# main.net
KiCad netlist of a schematic drawn in EAGLE
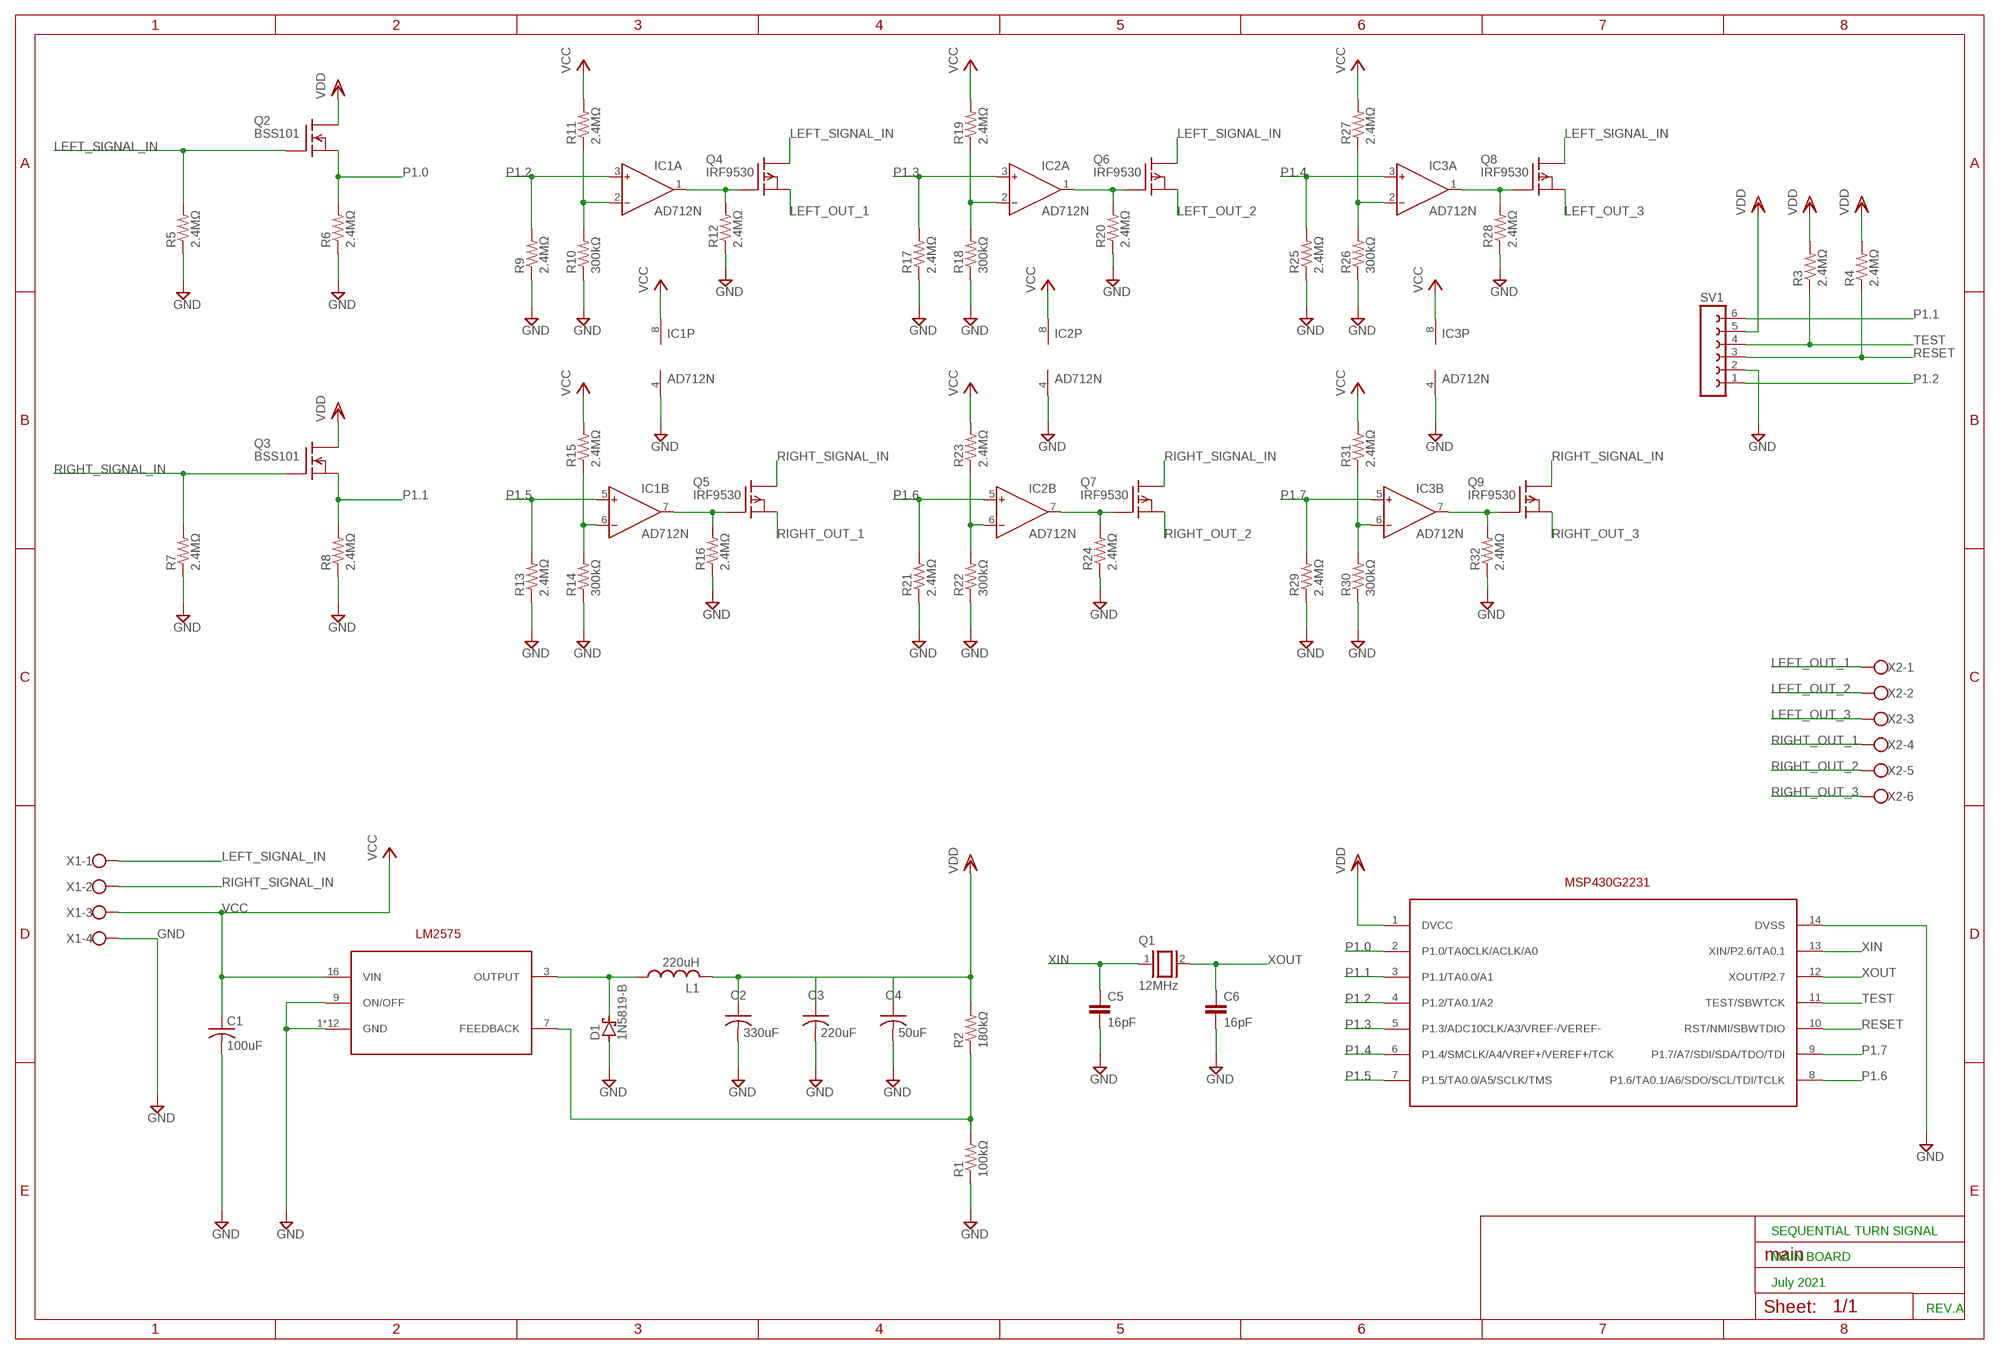
[diagram p0: schematic, sheet 1]

(export (version "E")
  (design (tool "Eeschema 10.0.6"))
  (components
    (comp (ref "C1")
      (value "100uF")
      (footprint "eagle-import:C025-050X050")
      (libsource (lib "eagle-import") (part "C-US025-050X050"))
    )
    (comp (ref "C2")
      (value "330uF")
      (footprint "eagle-import:C025-050X050")
      (libsource (lib "eagle-import") (part "C-US025-050X050"))
    )
    (comp (ref "C3")
      (value "220uF")
      (footprint "eagle-import:C025-050X050")
      (libsource (lib "eagle-import") (part "C-US025-050X050"))
    )
    (comp (ref "C4")
      (value "50uF")
      (footprint "eagle-import:C025-050X050")
      (libsource (lib "eagle-import") (part "C-US025-050X050"))
    )
    (comp (ref "C5")
      (value "16pF")
      (footprint "eagle-import:C025-024X044")
      (libsource (lib "eagle-import") (part "C-EU025-024X044"))
    )
    (comp (ref "C6")
      (value "16pF")
      (footprint "eagle-import:C025-024X044")
      (libsource (lib "eagle-import") (part "C-EU025-024X044"))
    )
    (comp (ref "D1")
      (value "1N5819-B")
      (footprint "eagle-import:DO41-7.6")
      (libsource (lib "eagle-import") (part "1N5819-B"))
    )
    (comp (ref "IC1")
      (value "AD712N")
      (footprint "eagle-import:DIL08")
      (fields (field (name "MF") "ALTERA CORPORATION") (field (name "MPN") "AD712JNZ"))
      (libsource (lib "eagle-import") (part "AD712N"))
    )
    (comp (ref "IC2")
      (value "AD712N")
      (footprint "eagle-import:DIL08")
      (fields (field (name "MF") "ALTERA CORPORATION") (field (name "MPN") "AD712JNZ"))
      (libsource (lib "eagle-import") (part "AD712N"))
    )
    (comp (ref "IC3")
      (value "AD712N")
      (footprint "eagle-import:DIL08")
      (fields (field (name "MF") "ALTERA CORPORATION") (field (name "MPN") "AD712JNZ"))
      (libsource (lib "eagle-import") (part "AD712N"))
    )
    (comp (ref "L1")
      (value "220uH")
      (footprint "eagle-import:6000-XXXX-RC")
      (libsource (lib "eagle-import") (part "L-US6000-XXX-RC"))
    )
    (comp (ref "Q1")
      (value "12MHz")
      (footprint "eagle-import:Q")
      (libsource (lib "eagle-import") (part "XTAL"))
    )
    (comp (ref "Q2")
      (value "BSS101")
      (footprint "eagle-import:TO92")
      (libsource (lib "eagle-import") (part "BSS101"))
    )
    (comp (ref "Q3")
      (value "BSS101")
      (footprint "eagle-import:TO92")
      (libsource (lib "eagle-import") (part "BSS101"))
    )
    (comp (ref "Q4")
      (value "IRF9530")
      (footprint "eagle-import:TO220")
      (libsource (lib "eagle-import") (part "IRF9530"))
    )
    (comp (ref "Q5")
      (value "IRF9530")
      (footprint "eagle-import:TO220")
      (libsource (lib "eagle-import") (part "IRF9530"))
    )
    (comp (ref "Q6")
      (value "IRF9530")
      (footprint "eagle-import:TO220")
      (libsource (lib "eagle-import") (part "IRF9530"))
    )
    (comp (ref "Q7")
      (value "IRF9530")
      (footprint "eagle-import:TO220")
      (libsource (lib "eagle-import") (part "IRF9530"))
    )
    (comp (ref "Q8")
      (value "IRF9530")
      (footprint "eagle-import:TO220")
      (libsource (lib "eagle-import") (part "IRF9530"))
    )
    (comp (ref "Q9")
      (value "IRF9530")
      (footprint "eagle-import:TO220")
      (libsource (lib "eagle-import") (part "IRF9530"))
    )
    (comp (ref "R1")
      (value "100kΩ")
      (footprint "eagle-import:0207_12")
      (libsource (lib "eagle-import") (part "R-US_0207/12"))
    )
    (comp (ref "R2")
      (value "180kΩ")
      (footprint "eagle-import:0207_12")
      (libsource (lib "eagle-import") (part "R-US_0207/12"))
    )
    (comp (ref "R3")
      (value "2.4MΩ")
      (footprint "eagle-import:0207_12")
      (libsource (lib "eagle-import") (part "R-US_0207/12"))
    )
    (comp (ref "R4")
      (value "2.4MΩ")
      (footprint "eagle-import:0207_12")
      (libsource (lib "eagle-import") (part "R-US_0207/12"))
    )
    (comp (ref "R5")
      (value "2.4MΩ")
      (footprint "eagle-import:0207_12")
      (libsource (lib "eagle-import") (part "R-US_0207/12"))
    )
    (comp (ref "R6")
      (value "2.4MΩ")
      (footprint "eagle-import:0207_12")
      (libsource (lib "eagle-import") (part "R-US_0207/12"))
    )
    (comp (ref "R7")
      (value "2.4MΩ")
      (footprint "eagle-import:0207_12")
      (libsource (lib "eagle-import") (part "R-US_0207/12"))
    )
    (comp (ref "R8")
      (value "2.4MΩ")
      (footprint "eagle-import:0207_12")
      (libsource (lib "eagle-import") (part "R-US_0207/12"))
    )
    (comp (ref "R9")
      (value "2.4MΩ")
      (footprint "eagle-import:0207_12")
      (libsource (lib "eagle-import") (part "R-US_0207/12"))
    )
    (comp (ref "R10")
      (value "300kΩ")
      (footprint "eagle-import:0207_12")
      (libsource (lib "eagle-import") (part "R-US_0207/12"))
    )
    (comp (ref "R11")
      (value "2.4MΩ")
      (footprint "eagle-import:0207_12")
      (libsource (lib "eagle-import") (part "R-US_0207/12"))
    )
    (comp (ref "R12")
      (value "2.4MΩ")
      (footprint "eagle-import:0207_12")
      (libsource (lib "eagle-import") (part "R-US_0207/12"))
    )
    (comp (ref "R13")
      (value "2.4MΩ")
      (footprint "eagle-import:0207_12")
      (libsource (lib "eagle-import") (part "R-US_0207/12"))
    )
    (comp (ref "R14")
      (value "300kΩ")
      (footprint "eagle-import:0207_12")
      (libsource (lib "eagle-import") (part "R-US_0207/12"))
    )
    (comp (ref "R15")
      (value "2.4MΩ")
      (footprint "eagle-import:0207_12")
      (libsource (lib "eagle-import") (part "R-US_0207/12"))
    )
    (comp (ref "R16")
      (value "2.4MΩ")
      (footprint "eagle-import:0207_12")
      (libsource (lib "eagle-import") (part "R-US_0207/12"))
    )
    (comp (ref "R17")
      (value "2.4MΩ")
      (footprint "eagle-import:0207_12")
      (libsource (lib "eagle-import") (part "R-US_0207/12"))
    )
    (comp (ref "R18")
      (value "300kΩ")
      (footprint "eagle-import:0207_12")
      (libsource (lib "eagle-import") (part "R-US_0207/12"))
    )
    (comp (ref "R19")
      (value "2.4MΩ")
      (footprint "eagle-import:0207_12")
      (libsource (lib "eagle-import") (part "R-US_0207/12"))
    )
    (comp (ref "R20")
      (value "2.4MΩ")
      (footprint "eagle-import:0207_12")
      (libsource (lib "eagle-import") (part "R-US_0207/12"))
    )
    (comp (ref "R21")
      (value "2.4MΩ")
      (footprint "eagle-import:0207_12")
      (libsource (lib "eagle-import") (part "R-US_0207/12"))
    )
    (comp (ref "R22")
      (value "300kΩ")
      (footprint "eagle-import:0207_12")
      (libsource (lib "eagle-import") (part "R-US_0207/12"))
    )
    (comp (ref "R23")
      (value "2.4MΩ")
      (footprint "eagle-import:0207_12")
      (libsource (lib "eagle-import") (part "R-US_0207/12"))
    )
    (comp (ref "R24")
      (value "2.4MΩ")
      (footprint "eagle-import:0207_12")
      (libsource (lib "eagle-import") (part "R-US_0207/12"))
    )
    (comp (ref "R25")
      (value "2.4MΩ")
      (footprint "eagle-import:0207_12")
      (libsource (lib "eagle-import") (part "R-US_0207/12"))
    )
    (comp (ref "R26")
      (value "300kΩ")
      (footprint "eagle-import:0207_12")
      (libsource (lib "eagle-import") (part "R-US_0207/12"))
    )
    (comp (ref "R27")
      (value "2.4MΩ")
      (footprint "eagle-import:0207_12")
      (libsource (lib "eagle-import") (part "R-US_0207/12"))
    )
    (comp (ref "R28")
      (value "2.4MΩ")
      (footprint "eagle-import:0207_12")
      (libsource (lib "eagle-import") (part "R-US_0207/12"))
    )
    (comp (ref "R29")
      (value "2.4MΩ")
      (footprint "eagle-import:0207_12")
      (libsource (lib "eagle-import") (part "R-US_0207/12"))
    )
    (comp (ref "R30")
      (value "300kΩ")
      (footprint "eagle-import:0207_12")
      (libsource (lib "eagle-import") (part "R-US_0207/12"))
    )
    (comp (ref "R31")
      (value "2.4MΩ")
      (footprint "eagle-import:0207_12")
      (libsource (lib "eagle-import") (part "R-US_0207/12"))
    )
    (comp (ref "R32")
      (value "2.4MΩ")
      (footprint "eagle-import:0207_12")
      (libsource (lib "eagle-import") (part "R-US_0207/12"))
    )
    (comp (ref "SV1")
      (value "FE06-1")
      (footprint "eagle-import:FE06")
      (libsource (lib "eagle-import") (part "FE06-1"))
    )
    (comp (ref "U$1")
      (value "MSP430G2231PDIP14")
      (footprint "eagle-import:DIP762W53P254L1969H508Q14B")
      (libsource (lib "eagle-import") (part "MSP430G2231PDIP14"))
    )
    (comp (ref "U$2")
      (value "LM2575PDIP16")
      (footprint "eagle-import:DIP762W53P254L1969H508Q16B")
      (libsource (lib "eagle-import") (part "LM2575PDIP16"))
    )
    (comp (ref "X1")
      (value "W237-4")
      (footprint "eagle-import:W237-4")
      (libsource (lib "eagle-import") (part "W237-4"))
    )
    (comp (ref "X2")
      (value "W237-6")
      (footprint "eagle-import:W237-6")
      (libsource (lib "eagle-import") (part "W237-6"))
    )
  )
  (nets
    (net (code "1") (name "/LEFT_OUT_1") (class "Default")
      (node (ref "Q4") (pin "3") (pinfunction "S_3") (pintype "passive"))
      (node (ref "X2") (pin "1") (pinfunction "KL_1") (pintype "passive"))
    )
    (net (code "2") (name "/LEFT_OUT_2") (class "Default")
      (node (ref "Q6") (pin "3") (pinfunction "S_3") (pintype "passive"))
      (node (ref "X2") (pin "2") (pinfunction "KL_2") (pintype "passive"))
    )
    (net (code "3") (name "/LEFT_OUT_3") (class "Default")
      (node (ref "Q8") (pin "3") (pinfunction "S_3") (pintype "passive"))
      (node (ref "X2") (pin "3") (pinfunction "KL_3") (pintype "passive"))
    )
    (net (code "4") (name "/LEFT_SIGNAL_IN") (class "Default")
      (node (ref "Q2") (pin "2") (pinfunction "G_2") (pintype "passive"))
      (node (ref "Q4") (pin "2") (pinfunction "D_2") (pintype "passive"))
      (node (ref "Q6") (pin "2") (pinfunction "D_2") (pintype "passive"))
      (node (ref "Q8") (pin "2") (pinfunction "D_2") (pintype "passive"))
      (node (ref "R5") (pin "2") (pinfunction "2_2") (pintype "passive"))
      (node (ref "X1") (pin "1") (pinfunction "KL_1") (pintype "passive"))
    )
    (net (code "5") (name "/P1.0") (class "Default")
      (node (ref "Q2") (pin "1") (pinfunction "S_1") (pintype "passive"))
      (node (ref "R6") (pin "2") (pinfunction "2_2") (pintype "passive"))
      (node (ref "U$1") (pin "2") (pinfunction "P1.0/TA0CLK/ACLK/A0_2") (pintype "bidirectional"))
    )
    (net (code "6") (name "/P1.1") (class "Default")
      (node (ref "Q3") (pin "1") (pinfunction "S_1") (pintype "passive"))
      (node (ref "R8") (pin "2") (pinfunction "2_2") (pintype "passive"))
      (node (ref "SV1") (pin "6") (pinfunction "6_6") (pintype "passive"))
      (node (ref "U$1") (pin "3") (pinfunction "P1.1/TA0.0/A1_3") (pintype "bidirectional"))
    )
    (net (code "7") (name "/P1.2") (class "Default")
      (node (ref "IC1") (pin "3") (pinfunction "IN+_3") (pintype "input"))
      (node (ref "R9") (pin "2") (pinfunction "2_2") (pintype "passive"))
      (node (ref "SV1") (pin "1") (pinfunction "1_1") (pintype "passive"))
      (node (ref "U$1") (pin "4") (pinfunction "P1.2/TA0.1/A2_4") (pintype "bidirectional"))
    )
    (net (code "8") (name "/P1.3") (class "Default")
      (node (ref "IC2") (pin "3") (pinfunction "IN+_3") (pintype "input"))
      (node (ref "R17") (pin "2") (pinfunction "2_2") (pintype "passive"))
      (node (ref "U$1") (pin "5") (pinfunction "P1.3/ADC10CLK/A3/VREF-/VEREF-_5") (pintype "bidirectional"))
    )
    (net (code "9") (name "/P1.4") (class "Default")
      (node (ref "IC3") (pin "3") (pinfunction "IN+_3") (pintype "input"))
      (node (ref "R25") (pin "2") (pinfunction "2_2") (pintype "passive"))
      (node (ref "U$1") (pin "6") (pinfunction "P1.4/SMCLK/A4/VREF+/VEREF+/TCK_6") (pintype "bidirectional"))
    )
    (net (code "10") (name "/P1.5") (class "Default")
      (node (ref "IC1") (pin "5") (pinfunction "IN+_5") (pintype "input"))
      (node (ref "R13") (pin "2") (pinfunction "2_2") (pintype "passive"))
      (node (ref "U$1") (pin "7") (pinfunction "P1.5/TA0.0/A5/SCLK/TMS_7") (pintype "bidirectional"))
    )
    (net (code "11") (name "/P1.6") (class "Default")
      (node (ref "IC2") (pin "5") (pinfunction "IN+_5") (pintype "input"))
      (node (ref "R21") (pin "2") (pinfunction "2_2") (pintype "passive"))
      (node (ref "U$1") (pin "8") (pinfunction "P1.6/TA0.1/A6/SDO/SCL/TDI/TCLK_8") (pintype "bidirectional"))
    )
    (net (code "12") (name "/P1.7") (class "Default")
      (node (ref "IC3") (pin "5") (pinfunction "IN+_5") (pintype "input"))
      (node (ref "R29") (pin "2") (pinfunction "2_2") (pintype "passive"))
      (node (ref "U$1") (pin "9") (pinfunction "P1.7/A7/SDI/SDA/TDO/TDI_9") (pintype "bidirectional"))
    )
    (net (code "13") (name "/RESET") (class "Default")
      (node (ref "R4") (pin "1") (pinfunction "1_1") (pintype "passive"))
      (node (ref "SV1") (pin "3") (pinfunction "3_3") (pintype "passive"))
      (node (ref "U$1") (pin "10") (pinfunction "RST/NMI/SBWTDIO_10") (pintype "bidirectional"))
    )
    (net (code "14") (name "/RIGHT_OUT_1") (class "Default")
      (node (ref "Q5") (pin "3") (pinfunction "S_3") (pintype "passive"))
      (node (ref "X2") (pin "4") (pinfunction "KL_4") (pintype "passive"))
    )
    (net (code "15") (name "/RIGHT_OUT_2") (class "Default")
      (node (ref "Q7") (pin "3") (pinfunction "S_3") (pintype "passive"))
      (node (ref "X2") (pin "5") (pinfunction "KL_5") (pintype "passive"))
    )
    (net (code "16") (name "/RIGHT_OUT_3") (class "Default")
      (node (ref "Q9") (pin "3") (pinfunction "S_3") (pintype "passive"))
      (node (ref "X2") (pin "6") (pinfunction "KL_6") (pintype "passive"))
    )
    (net (code "17") (name "/RIGHT_SIGNAL_IN") (class "Default")
      (node (ref "Q3") (pin "2") (pinfunction "G_2") (pintype "passive"))
      (node (ref "Q5") (pin "2") (pinfunction "D_2") (pintype "passive"))
      (node (ref "Q7") (pin "2") (pinfunction "D_2") (pintype "passive"))
      (node (ref "Q9") (pin "2") (pinfunction "D_2") (pintype "passive"))
      (node (ref "R7") (pin "2") (pinfunction "2_2") (pintype "passive"))
      (node (ref "X1") (pin "2") (pinfunction "KL_2") (pintype "passive"))
    )
    (net (code "18") (name "/TEST") (class "Default")
      (node (ref "R3") (pin "1") (pinfunction "1_1") (pintype "passive"))
      (node (ref "SV1") (pin "4") (pinfunction "4_4") (pintype "passive"))
      (node (ref "U$1") (pin "11") (pinfunction "TEST/SBWTCK_11") (pintype "bidirectional"))
    )
    (net (code "19") (name "/XIN") (class "Default")
      (node (ref "C5") (pin "1") (pinfunction "1_1") (pintype "passive"))
      (node (ref "Q1") (pin "1") (pinfunction "1_1") (pintype "passive"))
      (node (ref "U$1") (pin "13") (pinfunction "XIN/P2.6/TA0.1_13") (pintype "bidirectional"))
    )
    (net (code "20") (name "/XOUT") (class "Default")
      (node (ref "C6") (pin "1") (pinfunction "1_1") (pintype "passive"))
      (node (ref "Q1") (pin "2") (pinfunction "2_2") (pintype "passive"))
      (node (ref "U$1") (pin "12") (pinfunction "XOUT/P2.7_12") (pintype "bidirectional"))
    )
    (net (code "21") (name "GND") (class "Default")
      (node (ref "C1") (pin "2") (pinfunction "2_2") (pintype "passive"))
      (node (ref "C2") (pin "2") (pinfunction "2_2") (pintype "passive"))
      (node (ref "C3") (pin "2") (pinfunction "2_2") (pintype "passive"))
      (node (ref "C4") (pin "2") (pinfunction "2_2") (pintype "passive"))
      (node (ref "C5") (pin "2") (pinfunction "2_2") (pintype "passive"))
      (node (ref "C6") (pin "2") (pinfunction "2_2") (pintype "passive"))
      (node (ref "D1") (pin "A") (pinfunction "A_A") (pintype "passive"))
      (node (ref "IC1") (pin "4") (pinfunction "V-_4") (pintype "power_in"))
      (node (ref "IC2") (pin "4") (pinfunction "V-_4") (pintype "power_in"))
      (node (ref "IC3") (pin "4") (pinfunction "V-_4") (pintype "power_in"))
      (node (ref "R1") (pin "1") (pinfunction "1_1") (pintype "passive"))
      (node (ref "R10") (pin "1") (pinfunction "1_1") (pintype "passive"))
      (node (ref "R12") (pin "1") (pinfunction "1_1") (pintype "passive"))
      (node (ref "R13") (pin "1") (pinfunction "1_1") (pintype "passive"))
      (node (ref "R14") (pin "1") (pinfunction "1_1") (pintype "passive"))
      (node (ref "R16") (pin "1") (pinfunction "1_1") (pintype "passive"))
      (node (ref "R17") (pin "1") (pinfunction "1_1") (pintype "passive"))
      (node (ref "R18") (pin "1") (pinfunction "1_1") (pintype "passive"))
      (node (ref "R20") (pin "1") (pinfunction "1_1") (pintype "passive"))
      (node (ref "R21") (pin "1") (pinfunction "1_1") (pintype "passive"))
      (node (ref "R22") (pin "1") (pinfunction "1_1") (pintype "passive"))
      (node (ref "R24") (pin "1") (pinfunction "1_1") (pintype "passive"))
      (node (ref "R25") (pin "1") (pinfunction "1_1") (pintype "passive"))
      (node (ref "R26") (pin "1") (pinfunction "1_1") (pintype "passive"))
      (node (ref "R28") (pin "1") (pinfunction "1_1") (pintype "passive"))
      (node (ref "R29") (pin "1") (pinfunction "1_1") (pintype "passive"))
      (node (ref "R30") (pin "1") (pinfunction "1_1") (pintype "passive"))
      (node (ref "R32") (pin "1") (pinfunction "1_1") (pintype "passive"))
      (node (ref "R5") (pin "1") (pinfunction "1_1") (pintype "passive"))
      (node (ref "R6") (pin "1") (pinfunction "1_1") (pintype "passive"))
      (node (ref "R7") (pin "1") (pinfunction "1_1") (pintype "passive"))
      (node (ref "R8") (pin "1") (pinfunction "1_1") (pintype "passive"))
      (node (ref "R9") (pin "1") (pinfunction "1_1") (pintype "passive"))
      (node (ref "SV1") (pin "2") (pinfunction "2_2") (pintype "passive"))
      (node (ref "U$1") (pin "14") (pinfunction "DVSS_14") (pintype "bidirectional"))
      (node (ref "U$2") (pin "1") (pinfunction "GND_1") (pintype "bidirectional"))
      (node (ref "U$2") (pin "10") (pinfunction "GND_10") (pintype "bidirectional"))
      (node (ref "U$2") (pin "11") (pinfunction "GND_11") (pintype "bidirectional"))
      (node (ref "U$2") (pin "12") (pinfunction "GND_12") (pintype "bidirectional"))
      (node (ref "U$2") (pin "13") (pinfunction "GND_13") (pintype "bidirectional"))
      (node (ref "U$2") (pin "14") (pinfunction "GND_14") (pintype "bidirectional"))
      (node (ref "U$2") (pin "15") (pinfunction "GND_15") (pintype "bidirectional"))
      (node (ref "U$2") (pin "2") (pinfunction "GND_2") (pintype "bidirectional"))
      (node (ref "U$2") (pin "4") (pinfunction "GND_4") (pintype "bidirectional"))
      (node (ref "U$2") (pin "5") (pinfunction "GND_5") (pintype "bidirectional"))
      (node (ref "U$2") (pin "6") (pinfunction "GND_6") (pintype "bidirectional"))
      (node (ref "U$2") (pin "8") (pinfunction "GND_8") (pintype "bidirectional"))
      (node (ref "U$2") (pin "9") (pinfunction "ON/OFF_9") (pintype "bidirectional"))
      (node (ref "X1") (pin "4") (pinfunction "KL_4") (pintype "passive"))
    )
    (net (code "22") (name "Net-(IC1A-IN-)") (class "Default")
      (node (ref "IC1") (pin "2") (pinfunction "IN-_2") (pintype "input"))
      (node (ref "R10") (pin "2") (pinfunction "2_2") (pintype "passive"))
      (node (ref "R11") (pin "1") (pinfunction "1_1") (pintype "passive"))
    )
    (net (code "23") (name "Net-(IC1A-OUT)") (class "Default")
      (node (ref "IC1") (pin "1") (pinfunction "OUT_1") (pintype "output"))
      (node (ref "Q4") (pin "1") (pinfunction "G_1") (pintype "passive"))
      (node (ref "R12") (pin "2") (pinfunction "2_2") (pintype "passive"))
    )
    (net (code "24") (name "Net-(IC1B-IN-)") (class "Default")
      (node (ref "IC1") (pin "6") (pinfunction "IN-_6") (pintype "input"))
      (node (ref "R14") (pin "2") (pinfunction "2_2") (pintype "passive"))
      (node (ref "R15") (pin "1") (pinfunction "1_1") (pintype "passive"))
    )
    (net (code "25") (name "Net-(IC1B-OUT)") (class "Default")
      (node (ref "IC1") (pin "7") (pinfunction "OUT_7") (pintype "output"))
      (node (ref "Q5") (pin "1") (pinfunction "G_1") (pintype "passive"))
      (node (ref "R16") (pin "2") (pinfunction "2_2") (pintype "passive"))
    )
    (net (code "26") (name "Net-(IC2A-IN-)") (class "Default")
      (node (ref "IC2") (pin "2") (pinfunction "IN-_2") (pintype "input"))
      (node (ref "R18") (pin "2") (pinfunction "2_2") (pintype "passive"))
      (node (ref "R19") (pin "1") (pinfunction "1_1") (pintype "passive"))
    )
    (net (code "27") (name "Net-(IC2A-OUT)") (class "Default")
      (node (ref "IC2") (pin "1") (pinfunction "OUT_1") (pintype "output"))
      (node (ref "Q6") (pin "1") (pinfunction "G_1") (pintype "passive"))
      (node (ref "R20") (pin "2") (pinfunction "2_2") (pintype "passive"))
    )
    (net (code "28") (name "Net-(IC2B-IN-)") (class "Default")
      (node (ref "IC2") (pin "6") (pinfunction "IN-_6") (pintype "input"))
      (node (ref "R22") (pin "2") (pinfunction "2_2") (pintype "passive"))
      (node (ref "R23") (pin "1") (pinfunction "1_1") (pintype "passive"))
    )
    (net (code "29") (name "Net-(IC2B-OUT)") (class "Default")
      (node (ref "IC2") (pin "7") (pinfunction "OUT_7") (pintype "output"))
      (node (ref "Q7") (pin "1") (pinfunction "G_1") (pintype "passive"))
      (node (ref "R24") (pin "2") (pinfunction "2_2") (pintype "passive"))
    )
    (net (code "30") (name "Net-(IC3A-IN-)") (class "Default")
      (node (ref "IC3") (pin "2") (pinfunction "IN-_2") (pintype "input"))
      (node (ref "R26") (pin "2") (pinfunction "2_2") (pintype "passive"))
      (node (ref "R27") (pin "1") (pinfunction "1_1") (pintype "passive"))
    )
    (net (code "31") (name "Net-(IC3A-OUT)") (class "Default")
      (node (ref "IC3") (pin "1") (pinfunction "OUT_1") (pintype "output"))
      (node (ref "Q8") (pin "1") (pinfunction "G_1") (pintype "passive"))
      (node (ref "R28") (pin "2") (pinfunction "2_2") (pintype "passive"))
    )
    (net (code "32") (name "Net-(IC3B-IN-)") (class "Default")
      (node (ref "IC3") (pin "6") (pinfunction "IN-_6") (pintype "input"))
      (node (ref "R30") (pin "2") (pinfunction "2_2") (pintype "passive"))
      (node (ref "R31") (pin "1") (pinfunction "1_1") (pintype "passive"))
    )
    (net (code "33") (name "Net-(IC3B-OUT)") (class "Default")
      (node (ref "IC3") (pin "7") (pinfunction "OUT_7") (pintype "output"))
      (node (ref "Q9") (pin "1") (pinfunction "G_1") (pintype "passive"))
      (node (ref "R32") (pin "2") (pinfunction "2_2") (pintype "passive"))
    )
    (net (code "34") (name "Net-(U$2-FEEDBACK)") (class "Default")
      (node (ref "R1") (pin "2") (pinfunction "2_2") (pintype "passive"))
      (node (ref "R2") (pin "1") (pinfunction "1_1") (pintype "passive"))
      (node (ref "U$2") (pin "7") (pinfunction "FEEDBACK_7") (pintype "bidirectional"))
    )
    (net (code "35") (name "Net-(U$2-OUTPUT)") (class "Default")
      (node (ref "D1") (pin "C") (pinfunction "C_C") (pintype "passive"))
      (node (ref "L1") (pin "1") (pinfunction "1_1") (pintype "passive"))
      (node (ref "U$2") (pin "3") (pinfunction "OUTPUT_3") (pintype "bidirectional"))
    )
    (net (code "36") (name "VCC") (class "Default")
      (node (ref "C1") (pin "1") (pinfunction "1_1") (pintype "passive"))
      (node (ref "IC1") (pin "8") (pinfunction "V+_8") (pintype "power_in"))
      (node (ref "IC2") (pin "8") (pinfunction "V+_8") (pintype "power_in"))
      (node (ref "IC3") (pin "8") (pinfunction "V+_8") (pintype "power_in"))
      (node (ref "R11") (pin "2") (pinfunction "2_2") (pintype "passive"))
      (node (ref "R15") (pin "2") (pinfunction "2_2") (pintype "passive"))
      (node (ref "R19") (pin "2") (pinfunction "2_2") (pintype "passive"))
      (node (ref "R23") (pin "2") (pinfunction "2_2") (pintype "passive"))
      (node (ref "R27") (pin "2") (pinfunction "2_2") (pintype "passive"))
      (node (ref "R31") (pin "2") (pinfunction "2_2") (pintype "passive"))
      (node (ref "U$2") (pin "16") (pinfunction "VIN_16") (pintype "bidirectional"))
      (node (ref "X1") (pin "3") (pinfunction "KL_3") (pintype "passive"))
    )
    (net (code "37") (name "VDD") (class "Default")
      (node (ref "C2") (pin "1") (pinfunction "1_1") (pintype "passive"))
      (node (ref "L1") (pin "2") (pinfunction "2_2") (pintype "passive"))
      (node (ref "Q2") (pin "3") (pinfunction "D_3") (pintype "passive"))
      (node (ref "Q3") (pin "3") (pinfunction "D_3") (pintype "passive"))
      (node (ref "R2") (pin "2") (pinfunction "2_2") (pintype "passive"))
      (node (ref "R3") (pin "2") (pinfunction "2_2") (pintype "passive"))
      (node (ref "R4") (pin "2") (pinfunction "2_2") (pintype "passive"))
      (node (ref "SV1") (pin "5") (pinfunction "5_5") (pintype "passive"))
      (node (ref "U$1") (pin "1") (pinfunction "DVCC_1") (pintype "bidirectional"))
    )
    (net (code "38") (name "unconnected-(C3-Pad1)") (class "Default")
      (node (ref "C3") (pin "1") (pinfunction "1_1") (pintype "passive"))
    )
    (net (code "39") (name "unconnected-(C4-Pad1)") (class "Default")
      (node (ref "C4") (pin "1") (pinfunction "1_1") (pintype "passive"))
    )
  )
)
